# LB_BIT_o6_BUZZER-v02_rev1.net
KiCad netlist of a schematic drawn in EAGLE
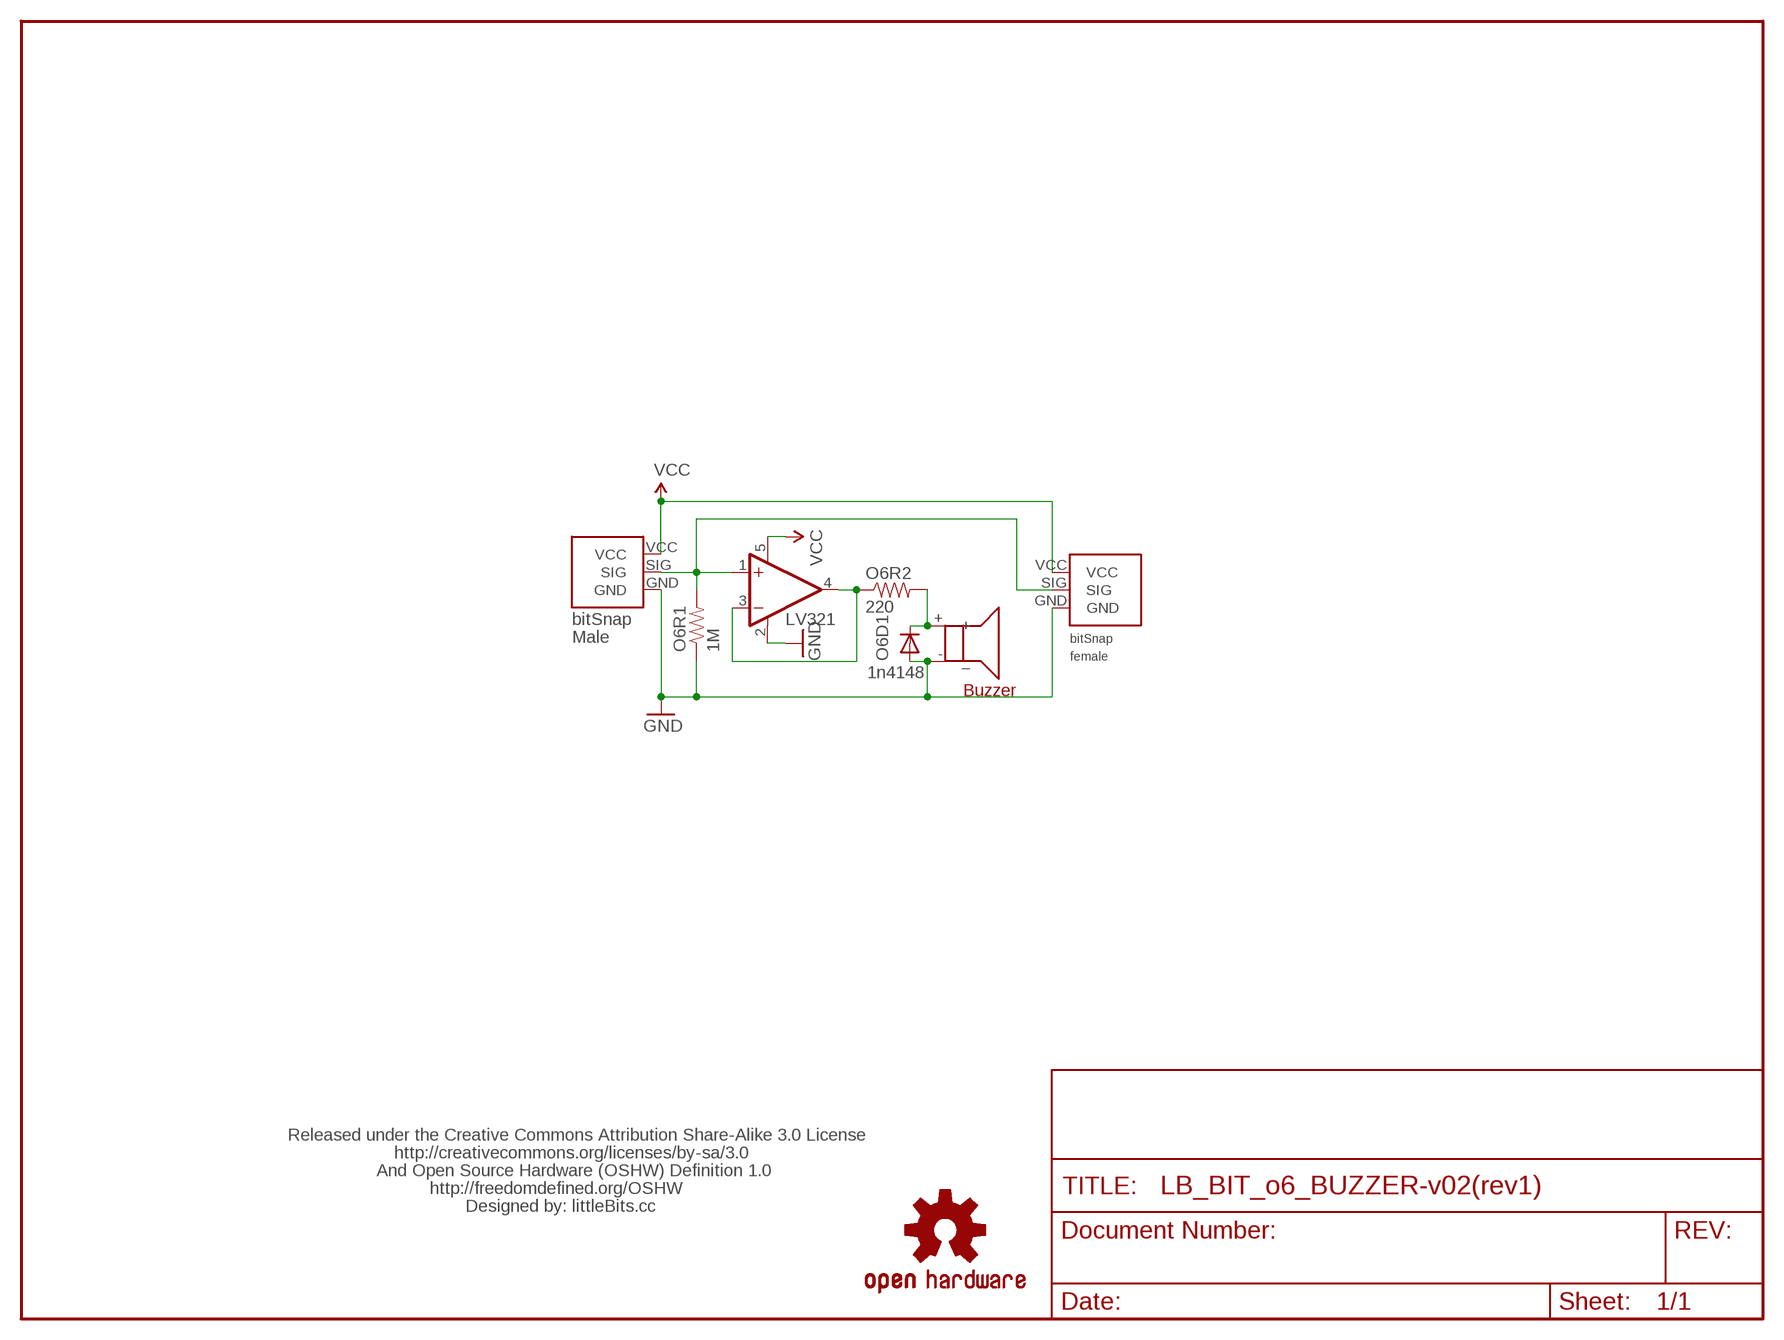
[diagram p0: schematic, sheet 1]

(export (version "E")
  (design (tool "Eeschema 10.0.6"))
  (components
    (comp (ref "O6BSF")
      (value "BITSNAP_FEMALE")
      (footprint "eagle-import:BITSNAP_FEMALE")
      (libsource (lib "eagle-import") (part "BITSNAP_FEMALE"))
    )
    (comp (ref "O6BSM")
      (value "BITSNAP_MALE")
      (footprint "eagle-import:BITSNAP_MALE")
      (libsource (lib "eagle-import") (part "BITSNAP_MALE"))
    )
    (comp (ref "O6D1")
      (value "1n4148")
      (footprint "eagle-import:SOD-323")
      (libsource (lib "eagle-import") (part "DIODESOD"))
    )
    (comp (ref "O6R1")
      (value "1M")
      (footprint "eagle-import:0603-RES")
      (libsource (lib "eagle-import") (part "RESISTOR0603-RES"))
    )
    (comp (ref "O6R2")
      (value "220")
      (footprint "eagle-import:0603-RES")
      (libsource (lib "eagle-import") (part "RESISTOR0603-RES"))
    )
    (comp (ref "O6U1")
      (value "BUZZER-JSH2317AT")
      (footprint "eagle-import:BUZZER-JSH2317AT")
      (libsource (lib "eagle-import") (part "BUZZER-JSH2317AT"))
    )
    (comp (ref "U$2")
      (value "LV321")
      (footprint "eagle-import:SC70")
      (libsource (lib "eagle-import") (part "LV321"))
    )
    (comp (ref "U$15")
      (value "LB_CREDITS_V2")
      (footprint "eagle-import:LB_CREDITS_V2")
      (libsource (lib "eagle-import") (part "LB_CREDITS_V2"))
    )
    (comp (ref "U$16")
      (value "OSHW-LOGOL")
      (footprint "eagle-import:OSHW-LOGO-L")
      (libsource (lib "eagle-import") (part "OSHW-LOGOL"))
    )
  )
  (nets
    (net (code "1") (name "GND") (class "Default")
      (node (ref "O6BSF") (pin "GND") (pinfunction "GND_GND") (pintype "bidirectional"))
      (node (ref "O6BSM") (pin "GND") (pinfunction "GND_GND") (pintype "bidirectional"))
      (node (ref "O6D1") (pin "2") (pinfunction "A_2") (pintype "passive"))
      (node (ref "O6R1") (pin "1") (pinfunction "1_1") (pintype "passive"))
      (node (ref "O6U1") (pin "-") (pinfunction "__-") (pintype "bidirectional"))
      (node (ref "U$2") (pin "2") (pinfunction "V-_2") (pintype "power_in"))
    )
    (net (code "2") (name "Net-(O6D1-C)") (class "Default")
      (node (ref "O6D1") (pin "1") (pinfunction "C_1") (pintype "passive"))
      (node (ref "O6R2") (pin "2") (pinfunction "2_2") (pintype "passive"))
      (node (ref "O6U1") (pin "+") (pinfunction "+_+") (pintype "bidirectional"))
    )
    (net (code "3") (name "Net-(U$2-+IN)") (class "Default")
      (node (ref "O6BSF") (pin "SIG") (pinfunction "SIG_SIG") (pintype "bidirectional"))
      (node (ref "O6BSM") (pin "SIG") (pinfunction "SIG_SIG") (pintype "bidirectional"))
      (node (ref "O6R1") (pin "2") (pinfunction "2_2") (pintype "passive"))
      (node (ref "U$2") (pin "1") (pinfunction "+IN_1") (pintype "input"))
    )
    (net (code "4") (name "Net-(U$2--IN)") (class "Default")
      (node (ref "O6R2") (pin "1") (pinfunction "1_1") (pintype "passive"))
      (node (ref "U$2") (pin "3") (pinfunction "-IN_3") (pintype "input"))
      (node (ref "U$2") (pin "4") (pinfunction "OUT_4") (pintype "output"))
    )
    (net (code "5") (name "VCC") (class "Default")
      (node (ref "O6BSF") (pin "VCC") (pinfunction "VCC_VCC") (pintype "bidirectional"))
      (node (ref "O6BSM") (pin "VCC") (pinfunction "VCC_VCC") (pintype "bidirectional"))
      (node (ref "U$2") (pin "5") (pinfunction "V+_5") (pintype "power_in"))
    )
  )
)
